# X15_Power_Plate.net
KiCad netlist of a schematic drawn in EAGLE
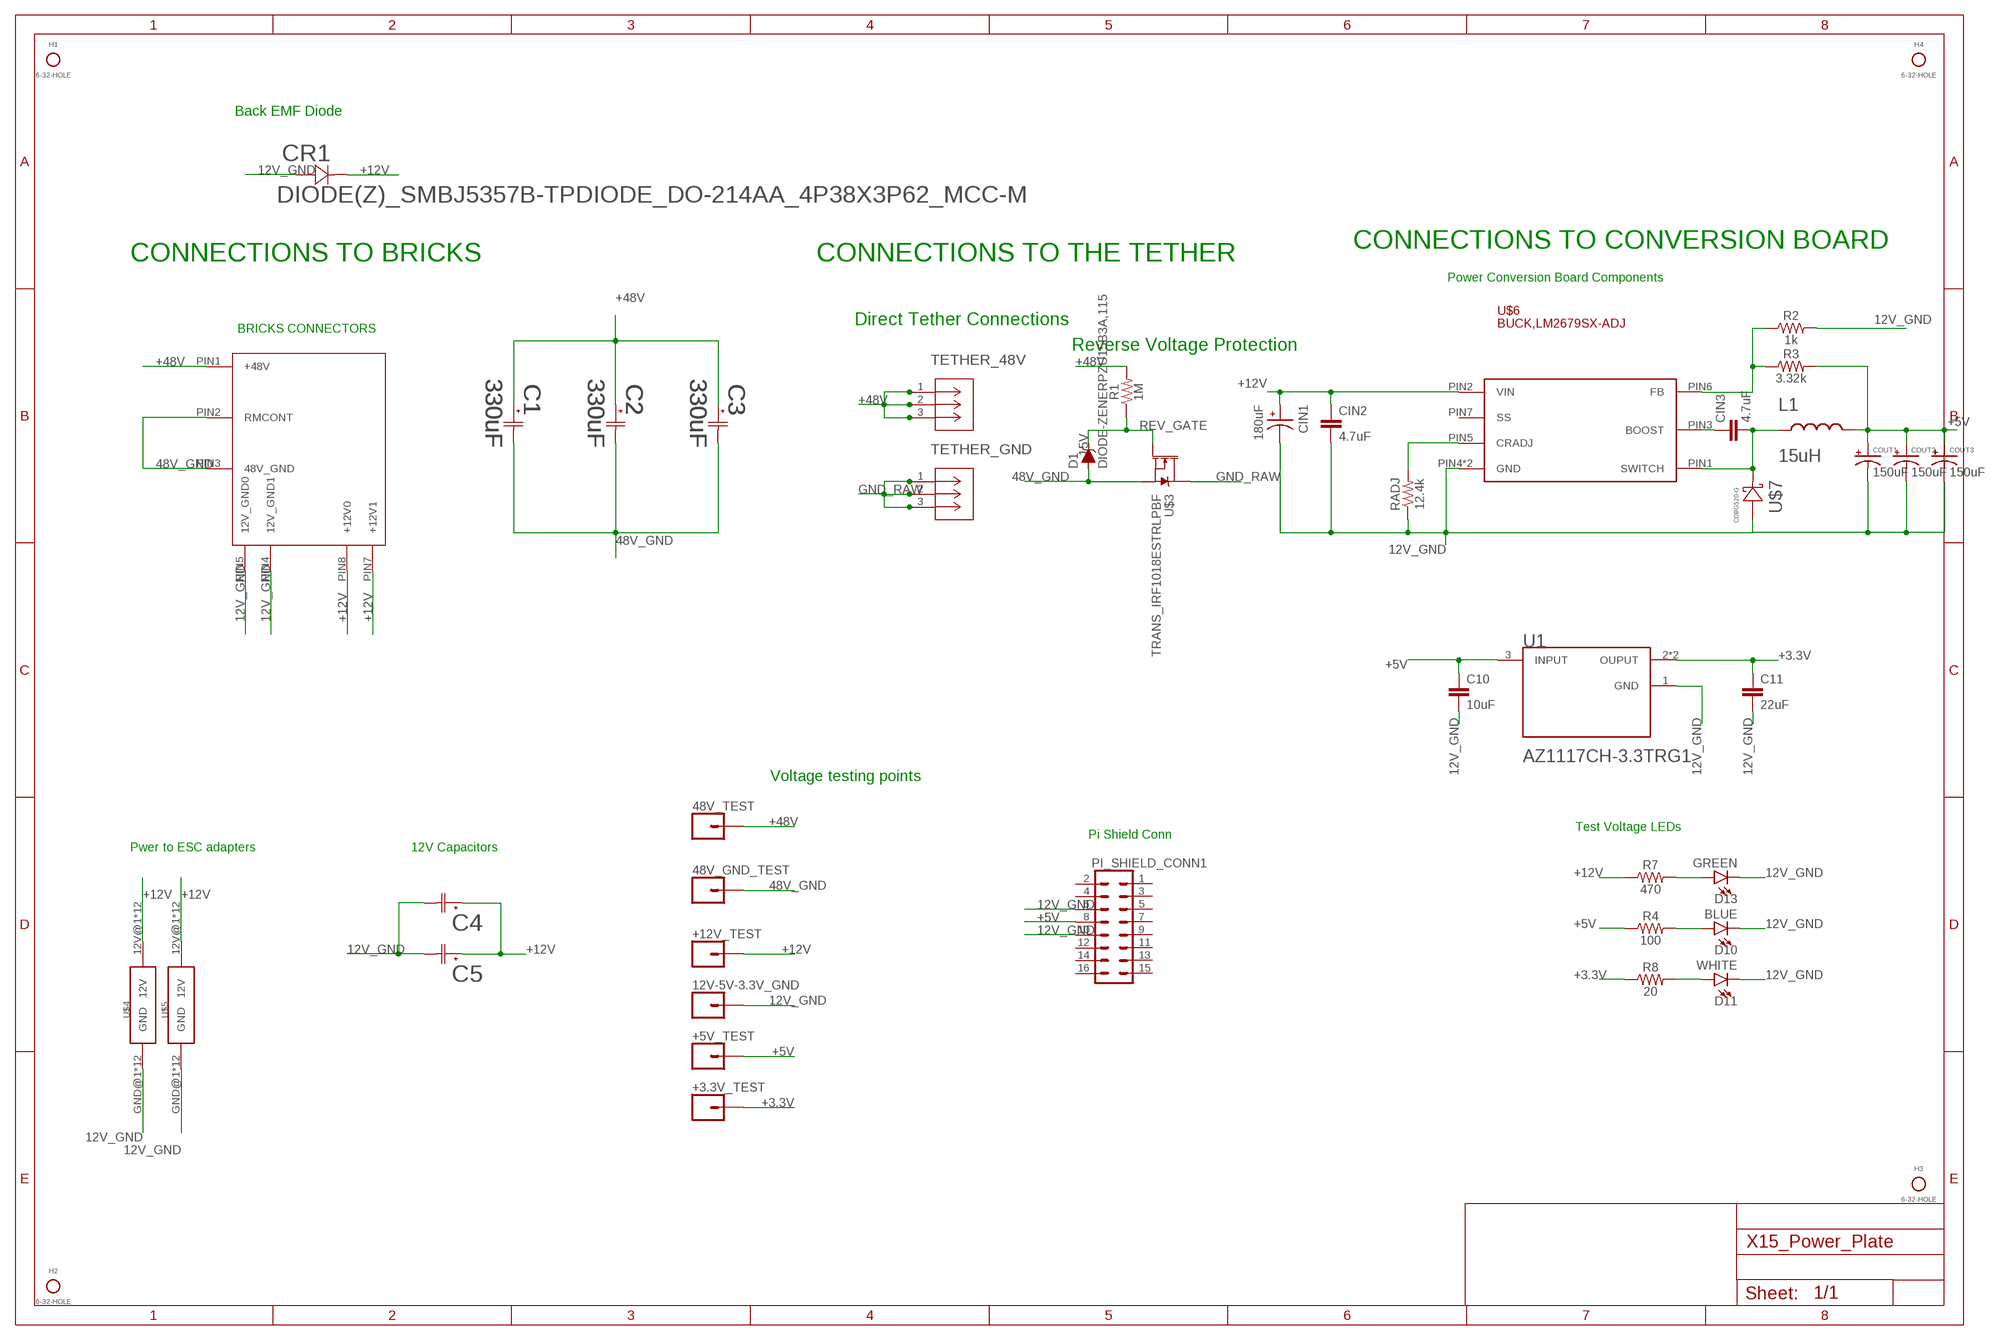
[diagram p0: schematic, sheet 1]

(export (version "E")
  (design (tool "Eeschema 10.0.6"))
  (components
    (comp (ref "+3.3V_TEST")
      (value "CONN_01")
      (footprint "eagle-import:1X01")
      (libsource (lib "eagle-import") (part "CONN_01"))
    )
    (comp (ref "+5V_TEST")
      (value "CONN_01")
      (footprint "eagle-import:1X01")
      (libsource (lib "eagle-import") (part "CONN_01"))
    )
    (comp (ref "+12V_TEST")
      (value "CONN_01")
      (footprint "eagle-import:1X01")
      (libsource (lib "eagle-import") (part "CONN_01"))
    )
    (comp (ref "12V-5V-3.3V_GND")
      (value "CONN_01")
      (footprint "eagle-import:1X01")
      (libsource (lib "eagle-import") (part "CONN_01"))
    )
    (comp (ref "48V_GND_TEST")
      (value "CONN_01")
      (footprint "eagle-import:1X01")
      (libsource (lib "eagle-import") (part "CONN_01"))
    )
    (comp (ref "48V_TEST")
      (value "CONN_01")
      (footprint "eagle-import:1X01")
      (libsource (lib "eagle-import") (part "CONN_01"))
    )
    (comp (ref "C1")
      (value "330uF")
      (footprint "eagle-import:CAP_099112E3_VIS-M")
      (fields
        (field (name "MANUFACTURER_PART_NUMBER") "MAL215099112E3")
        (field (name "COPYRIGHT") "Copyright (C) 2022 Ultra Librarian. All rights reserved.")
      )
      (libsource (lib "eagle-import") (part "CAP_MAL215099112E3CAP_099112E3_VIS-M"))
    )
    (comp (ref "C2")
      (value "330uF")
      (footprint "eagle-import:CAP_099112E3_VIS-M")
      (fields
        (field (name "MANUFACTURER_PART_NUMBER") "MAL215099112E3")
        (field (name "COPYRIGHT") "Copyright (C) 2022 Ultra Librarian. All rights reserved.")
      )
      (libsource (lib "eagle-import") (part "CAP_MAL215099112E3CAP_099112E3_VIS-M"))
    )
    (comp (ref "C3")
      (value "330uF")
      (footprint "eagle-import:CAP_099112E3_VIS-M")
      (fields
        (field (name "MANUFACTURER_PART_NUMBER") "MAL215099112E3")
        (field (name "COPYRIGHT") "Copyright (C) 2022 Ultra Librarian. All rights reserved.")
      )
      (libsource (lib "eagle-import") (part "CAP_MAL215099112E3CAP_099112E3_VIS-M"))
    )
    (comp (ref "C4")
      (value "UCV1E561MNL1GSCAP_UCD_8X10_NCH")
      (footprint "eagle-import:CAP_UCD_8X10_NCH")
      (fields
        (field (name "MANUFACTURER_PART_NUMBER") "UCV1E561MNL1GS")
        (field (name "COPYRIGHT") "Copyright (C) 2023 Ultra Librarian. All rights reserved.")
      )
      (libsource (lib "eagle-import") (part "UCV1E561MNL1GSCAP_UCD_8X10_NCH"))
    )
    (comp (ref "C5")
      (value "UCV1E561MNL1GSCAP_UCD_8X10_NCH")
      (footprint "eagle-import:CAP_UCD_8X10_NCH")
      (fields
        (field (name "MANUFACTURER_PART_NUMBER") "UCV1E561MNL1GS")
        (field (name "COPYRIGHT") "Copyright (C) 2023 Ultra Librarian. All rights reserved.")
      )
      (libsource (lib "eagle-import") (part "UCV1E561MNL1GSCAP_UCD_8X10_NCH"))
    )
    (comp (ref "C10")
      (value "10uF")
      (footprint "eagle-import:0603")
      (libsource (lib "eagle-import") (part "4.7PF-0603-50V-5%"))
    )
    (comp (ref "C11")
      (value "22uF")
      (footprint "eagle-import:0603")
      (libsource (lib "eagle-import") (part "4.7PF-0603-50V-5%"))
    )
    (comp (ref "CIN1")
      (value "180uF")
      (footprint "eagle-import:CAP_EEEFKE181XSP")
      (fields
        (field (name "DIGI-KEY_PART_NUMBER") "P18956TR-ND")
        (field (name "MF") "Panasonic")
        (field (name "MP") "EEEFKE181XSP")
      )
      (libsource (lib "eagle-import") (part "EEEFKE181XSP"))
    )
    (comp (ref "CIN2")
      (value "4.7uF")
      (footprint "eagle-import:0603")
      (libsource (lib "eagle-import") (part "4.7UF0603"))
    )
    (comp (ref "CIN3")
      (value "4.7uF")
      (footprint "eagle-import:0603")
      (libsource (lib "eagle-import") (part "4.7UF0603"))
    )
    (comp (ref "COUT1")
      (value "150uF")
      (footprint "eagle-import:2917(7343-31-METRIC)")
      (libsource (lib "eagle-import") (part "C-TANTALUM(10UF_150UF)"))
    )
    (comp (ref "COUT2")
      (value "150uF")
      (footprint "eagle-import:2917(7343-31-METRIC)")
      (libsource (lib "eagle-import") (part "C-TANTALUM(10UF_150UF)"))
    )
    (comp (ref "COUT3")
      (value "150uF")
      (footprint "eagle-import:2917(7343-31-METRIC)")
      (libsource (lib "eagle-import") (part "C-TANTALUM(10UF_150UF)"))
    )
    (comp (ref "CR1")
      (value "DIODE(Z)_SMBJ5357B-TPDIODE_DO-214AA_4P38X3P62_MCC-M")
      (footprint "eagle-import:DIODE_DO-214AA_4P38X3P62_MCC-M")
      (fields
        (field (name "MANUFACTURER_PART_NUMBER") "SMBJ5357B-TP")
        (field (name "COPYRIGHT") "Copyright (C) 2022 Ultra Librarian. All rights reserved.")
      )
      (libsource (lib "eagle-import") (part "DIODE(Z)_SMBJ5357B-TPDIODE_DO-214AA_4P38X3P62_MCC-M"))
    )
    (comp (ref "D1")
      (value "DIODE-ZENERPZU15B3A,115")
      (footprint "eagle-import:SOD-323")
      (fields (field (name "ZENER_VOLTAGE") "15V"))
      (libsource (lib "eagle-import") (part "DIODE-ZENERPZU15B3A,115"))
    )
    (comp (ref "D10")
      (value "BLUE")
      (footprint "eagle-import:LED-0603")
      (libsource (lib "eagle-import") (part "LED-BLUE0603"))
    )
    (comp (ref "D11")
      (value "WHITE")
      (footprint "eagle-import:LED-0603")
      (libsource (lib "eagle-import") (part "LED-WHITE0603"))
    )
    (comp (ref "D13")
      (value "GREEN")
      (footprint "eagle-import:LED-0603")
      (libsource (lib "eagle-import") (part "LED-GREEN0603"))
    )
    (comp (ref "H1")
      (value "6-32-HOLE")
      (footprint "eagle-import:6-32-HOLE")
      (libsource (lib "eagle-import") (part "6-32-HOLE"))
    )
    (comp (ref "H2")
      (value "6-32-HOLE")
      (footprint "eagle-import:6-32-HOLE")
      (libsource (lib "eagle-import") (part "6-32-HOLE"))
    )
    (comp (ref "H3")
      (value "6-32-HOLE")
      (footprint "eagle-import:6-32-HOLE")
      (libsource (lib "eagle-import") (part "6-32-HOLE"))
    )
    (comp (ref "H4")
      (value "6-32-HOLE")
      (footprint "eagle-import:6-32-HOLE")
      (libsource (lib "eagle-import") (part "6-32-HOLE"))
    )
    (comp (ref "L1")
      (value "15uH")
      (footprint "eagle-import:HCMA1305")
      (libsource (lib "eagle-import") (part "HCMA1305"))
    )
    (comp (ref "PI_SHIELD_CONN1")
      (value "8X_CONN")
      (footprint "eagle-import:IPL7X2")
      (libsource (lib "eagle-import") (part "8X_CONN"))
    )
    (comp (ref "R1")
      (value "1M")
      (footprint "eagle-import:0603")
      (libsource (lib "eagle-import") (part "1MOHM-0603-1/4W-5%"))
    )
    (comp (ref "R2")
      (value "1k")
      (footprint "eagle-import:0603")
      (libsource (lib "eagle-import") (part "2.0KOHM-0603-1/10W-5%"))
    )
    (comp (ref "R3")
      (value "3.32k")
      (footprint "eagle-import:0603")
      (libsource (lib "eagle-import") (part "2.0KOHM-0603-1/10W-5%"))
    )
    (comp (ref "R4")
      (value "100")
      (footprint "eagle-import:0603")
      (libsource (lib "eagle-import") (part "100OHM-0603-1/4W-5%"))
    )
    (comp (ref "R7")
      (value "470")
      (footprint "eagle-import:0603")
      (libsource (lib "eagle-import") (part "470OHM-0603-1/10W-1%"))
    )
    (comp (ref "R8")
      (value "20")
      (footprint "eagle-import:0603")
      (libsource (lib "eagle-import") (part "20OHM-0603-1/10W-1%"))
    )
    (comp (ref "RADJ")
      (value "12.4k")
      (footprint "eagle-import:0603")
      (libsource (lib "eagle-import") (part "2.0KOHM-0603-1/10W-5%"))
    )
    (comp (ref "TETHER_48V")
      (value "796636-3(TETHER)")
      (footprint "eagle-import:CON3_P5MM_VER_TERM-BLK_TYC")
      (fields
        (field (name "MANUFACTURER_PART_NUMBER") "796636-3")
        (field (name "COPYRIGHT") "Copyright (C) 2022 Ultra Librarian. All rights reserved.")
      )
      (libsource (lib "eagle-import") (part "796636-3(TETHER)"))
    )
    (comp (ref "TETHER_GND")
      (value "796636-3(TETHER)")
      (footprint "eagle-import:CON3_P5MM_VER_TERM-BLK_TYC")
      (fields
        (field (name "MANUFACTURER_PART_NUMBER") "796636-3")
        (field (name "COPYRIGHT") "Copyright (C) 2022 Ultra Librarian. All rights reserved.")
      )
      (libsource (lib "eagle-import") (part "796636-3(TETHER)"))
    )
    (comp (ref "U$2")
      (value "CONN_BMR480_CONNECTOR")
      (footprint "eagle-import:BMR480_CONNECTOR")
      (libsource (lib "eagle-import") (part "CONN_BMR480_CONNECTOR"))
    )
    (comp (ref "U$3")
      (value "TRANS_IRF1018ESTRLPBF")
      (footprint "eagle-import:D2PAK")
      (libsource (lib "eagle-import") (part "TRANS_IRF1018EPBF"))
    )
    (comp (ref "U$4")
      (value "BACKPLANE_ESC_ADAPTER_PWRBKP")
      (footprint "eagle-import:BACKPLANE_ESC_ADAPTER_BKP_PWR")
      (libsource (lib "eagle-import") (part "BACKPLANE_ESC_ADAPTER_PWRBKP"))
    )
    (comp (ref "U$5")
      (value "BACKPLANE_ESC_ADAPTER_PWRBKP")
      (footprint "eagle-import:BACKPLANE_ESC_ADAPTER_BKP_PWR")
      (libsource (lib "eagle-import") (part "BACKPLANE_ESC_ADAPTER_PWRBKP"))
    )
    (comp (ref "U$6")
      (value "BUCK,LM2679SX-ADJ")
      (footprint "eagle-import:BUCK,LM2679SX-ADJ")
      (libsource (lib "eagle-import") (part "BUCK,LM2679SX-ADJ"))
    )
    (comp (ref "U$7")
      (value "CDBG520-G")
      (footprint "eagle-import:DO214AC")
      (libsource (lib "eagle-import") (part "CDBG520-G"))
    )
    (comp (ref "U1")
      (value "LINEAR,AZ1117CR-3.3TRG1DIODES_AZ1117CH-3.3TRG1_0_0")
      (footprint "eagle-import:LINEAR,AZ1117CR-3.3TRG1")
      (fields (field (name "MF") "Diodes Inc.") (field (name "MP") "AZ1117CH-3.3TRG1"))
      (libsource (lib "eagle-import") (part "LINEAR,AZ1117CR-3.3TRG1DIODES_AZ1117CH-3.3TRG1_0_0"))
    )
  )
  (nets
    (net (code "1") (name "/+3.3V") (class "Default")
      (node (ref "+3.3V_TEST") (pin "1") (pinfunction "1_1") (pintype "passive"))
      (node (ref "C11") (pin "1") (pinfunction "1_1") (pintype "passive"))
      (node (ref "R8") (pin "1") (pinfunction "1_1") (pintype "passive"))
      (node (ref "U1") (pin "2") (pinfunction "OUPUT_2") (pintype "output"))
      (node (ref "U1") (pin "4") (pinfunction "OUPUT_4") (pintype "output"))
    )
    (net (code "2") (name "/+5V") (class "Default")
      (node (ref "+5V_TEST") (pin "1") (pinfunction "1_1") (pintype "passive"))
      (node (ref "C10") (pin "1") (pinfunction "1_1") (pintype "passive"))
      (node (ref "COUT1") (pin "+") (pinfunction "+_+") (pintype "passive"))
      (node (ref "COUT2") (pin "+") (pinfunction "+_+") (pintype "passive"))
      (node (ref "COUT3") (pin "+") (pinfunction "+_+") (pintype "passive"))
      (node (ref "L1") (pin "2") (pinfunction "2_2") (pintype "passive"))
      (node (ref "PI_SHIELD_CONN1") (pin "8") (pinfunction "19_8") (pintype "passive"))
      (node (ref "R3") (pin "2") (pinfunction "2_2") (pintype "passive"))
      (node (ref "R4") (pin "1") (pinfunction "1_1") (pintype "passive"))
      (node (ref "U1") (pin "3") (pinfunction "INPUT_3") (pintype "input"))
    )
    (net (code "3") (name "/+12V") (class "Default")
      (node (ref "+12V_TEST") (pin "1") (pinfunction "1_1") (pintype "passive"))
      (node (ref "C4") (pin "1") (pinfunction "1_1") (pintype "passive"))
      (node (ref "C5") (pin "1") (pinfunction "1_1") (pintype "passive"))
      (node (ref "CIN1") (pin "1") (pinfunction "1_1") (pintype "passive"))
      (node (ref "CIN2") (pin "1") (pinfunction "1_1") (pintype "passive"))
      (node (ref "CR1") (pin "1") (pinfunction "1_1") (pintype "passive"))
      (node (ref "R7") (pin "1") (pinfunction "1_1") (pintype "passive"))
      (node (ref "U$2") (pin "PIN7") (pinfunction "+12V1_PIN7") (pintype "bidirectional"))
      (node (ref "U$2") (pin "PIN8") (pinfunction "+12V0_PIN8") (pintype "bidirectional"))
      (node (ref "U$4") (pin "12V@1") (pinfunction "12V_12V@1") (pintype "bidirectional"))
      (node (ref "U$4") (pin "12V@10") (pinfunction "12V_12V@10") (pintype "bidirectional"))
      (node (ref "U$4") (pin "12V@11") (pinfunction "12V_12V@11") (pintype "bidirectional"))
      (node (ref "U$4") (pin "12V@12") (pinfunction "12V_12V@12") (pintype "bidirectional"))
      (node (ref "U$4") (pin "12V@2") (pinfunction "12V_12V@2") (pintype "bidirectional"))
      (node (ref "U$4") (pin "12V@3") (pinfunction "12V_12V@3") (pintype "bidirectional"))
      (node (ref "U$4") (pin "12V@4") (pinfunction "12V_12V@4") (pintype "bidirectional"))
      (node (ref "U$4") (pin "12V@5") (pinfunction "12V_12V@5") (pintype "bidirectional"))
      (node (ref "U$4") (pin "12V@6") (pinfunction "12V_12V@6") (pintype "bidirectional"))
      (node (ref "U$4") (pin "12V@7") (pinfunction "12V_12V@7") (pintype "bidirectional"))
      (node (ref "U$4") (pin "12V@8") (pinfunction "12V_12V@8") (pintype "bidirectional"))
      (node (ref "U$4") (pin "12V@9") (pinfunction "12V_12V@9") (pintype "bidirectional"))
      (node (ref "U$5") (pin "12V@1") (pinfunction "12V_12V@1") (pintype "bidirectional"))
      (node (ref "U$5") (pin "12V@10") (pinfunction "12V_12V@10") (pintype "bidirectional"))
      (node (ref "U$5") (pin "12V@11") (pinfunction "12V_12V@11") (pintype "bidirectional"))
      (node (ref "U$5") (pin "12V@12") (pinfunction "12V_12V@12") (pintype "bidirectional"))
      (node (ref "U$5") (pin "12V@2") (pinfunction "12V_12V@2") (pintype "bidirectional"))
      (node (ref "U$5") (pin "12V@3") (pinfunction "12V_12V@3") (pintype "bidirectional"))
      (node (ref "U$5") (pin "12V@4") (pinfunction "12V_12V@4") (pintype "bidirectional"))
      (node (ref "U$5") (pin "12V@5") (pinfunction "12V_12V@5") (pintype "bidirectional"))
      (node (ref "U$5") (pin "12V@6") (pinfunction "12V_12V@6") (pintype "bidirectional"))
      (node (ref "U$5") (pin "12V@7") (pinfunction "12V_12V@7") (pintype "bidirectional"))
      (node (ref "U$5") (pin "12V@8") (pinfunction "12V_12V@8") (pintype "bidirectional"))
      (node (ref "U$5") (pin "12V@9") (pinfunction "12V_12V@9") (pintype "bidirectional"))
      (node (ref "U$6") (pin "PIN2") (pinfunction "VIN_PIN2") (pintype "bidirectional"))
    )
    (net (code "4") (name "/+48V") (class "Default")
      (node (ref "48V_TEST") (pin "1") (pinfunction "1_1") (pintype "passive"))
      (node (ref "C1") (pin "1") (pinfunction "1_1") (pintype "passive"))
      (node (ref "C2") (pin "1") (pinfunction "1_1") (pintype "passive"))
      (node (ref "C3") (pin "1") (pinfunction "1_1") (pintype "passive"))
      (node (ref "R1") (pin "2") (pinfunction "2_2") (pintype "passive"))
      (node (ref "TETHER_48V") (pin "1") (pinfunction "1_1") (pintype "passive"))
      (node (ref "TETHER_48V") (pin "2") (pinfunction "2_2") (pintype "passive"))
      (node (ref "TETHER_48V") (pin "3") (pinfunction "3_3") (pintype "passive"))
      (node (ref "U$2") (pin "PIN1") (pinfunction "+48V_PIN1") (pintype "bidirectional"))
    )
    (net (code "5") (name "/12V_GND") (class "Default")
      (node (ref "12V-5V-3.3V_GND") (pin "1") (pinfunction "1_1") (pintype "passive"))
      (node (ref "C10") (pin "2") (pinfunction "2_2") (pintype "passive"))
      (node (ref "C11") (pin "2") (pinfunction "2_2") (pintype "passive"))
      (node (ref "C4") (pin "2") (pinfunction "2_2") (pintype "passive"))
      (node (ref "C5") (pin "2") (pinfunction "2_2") (pintype "passive"))
      (node (ref "CIN1") (pin "2") (pinfunction "2_2") (pintype "passive"))
      (node (ref "CIN2") (pin "2") (pinfunction "2_2") (pintype "passive"))
      (node (ref "COUT1") (pin "-") (pinfunction "-_-") (pintype "passive"))
      (node (ref "COUT2") (pin "-") (pinfunction "-_-") (pintype "passive"))
      (node (ref "COUT3") (pin "-") (pinfunction "-_-") (pintype "passive"))
      (node (ref "CR1") (pin "2") (pinfunction "2_2") (pintype "passive"))
      (node (ref "D10") (pin "C") (pinfunction "C_C") (pintype "passive"))
      (node (ref "D11") (pin "C") (pinfunction "C_C") (pintype "passive"))
      (node (ref "D13") (pin "C") (pinfunction "C_C") (pintype "passive"))
      (node (ref "PI_SHIELD_CONN1") (pin "10") (pinfunction "21_10") (pintype "passive"))
      (node (ref "PI_SHIELD_CONN1") (pin "6") (pinfunction "17_6") (pintype "passive"))
      (node (ref "R2") (pin "2") (pinfunction "2_2") (pintype "passive"))
      (node (ref "RADJ") (pin "1") (pinfunction "1_1") (pintype "passive"))
      (node (ref "U$2") (pin "PIN4") (pinfunction "12V_GND1_PIN4") (pintype "bidirectional"))
      (node (ref "U$2") (pin "PIN5") (pinfunction "12V_GND0_PIN5") (pintype "bidirectional"))
      (node (ref "U$4") (pin "GND@1") (pinfunction "GND_GND@1") (pintype "bidirectional"))
      (node (ref "U$4") (pin "GND@10") (pinfunction "GND_GND@10") (pintype "bidirectional"))
      (node (ref "U$4") (pin "GND@11") (pinfunction "GND_GND@11") (pintype "bidirectional"))
      (node (ref "U$4") (pin "GND@12") (pinfunction "GND_GND@12") (pintype "bidirectional"))
      (node (ref "U$4") (pin "GND@2") (pinfunction "GND_GND@2") (pintype "bidirectional"))
      (node (ref "U$4") (pin "GND@3") (pinfunction "GND_GND@3") (pintype "bidirectional"))
      (node (ref "U$4") (pin "GND@4") (pinfunction "GND_GND@4") (pintype "bidirectional"))
      (node (ref "U$4") (pin "GND@5") (pinfunction "GND_GND@5") (pintype "bidirectional"))
      (node (ref "U$4") (pin "GND@6") (pinfunction "GND_GND@6") (pintype "bidirectional"))
      (node (ref "U$4") (pin "GND@7") (pinfunction "GND_GND@7") (pintype "bidirectional"))
      (node (ref "U$4") (pin "GND@8") (pinfunction "GND_GND@8") (pintype "bidirectional"))
      (node (ref "U$4") (pin "GND@9") (pinfunction "GND_GND@9") (pintype "bidirectional"))
      (node (ref "U$5") (pin "GND@1") (pinfunction "GND_GND@1") (pintype "bidirectional"))
      (node (ref "U$5") (pin "GND@10") (pinfunction "GND_GND@10") (pintype "bidirectional"))
      (node (ref "U$5") (pin "GND@11") (pinfunction "GND_GND@11") (pintype "bidirectional"))
      (node (ref "U$5") (pin "GND@12") (pinfunction "GND_GND@12") (pintype "bidirectional"))
      (node (ref "U$5") (pin "GND@2") (pinfunction "GND_GND@2") (pintype "bidirectional"))
      (node (ref "U$5") (pin "GND@3") (pinfunction "GND_GND@3") (pintype "bidirectional"))
      (node (ref "U$5") (pin "GND@4") (pinfunction "GND_GND@4") (pintype "bidirectional"))
      (node (ref "U$5") (pin "GND@5") (pinfunction "GND_GND@5") (pintype "bidirectional"))
      (node (ref "U$5") (pin "GND@6") (pinfunction "GND_GND@6") (pintype "bidirectional"))
      (node (ref "U$5") (pin "GND@7") (pinfunction "GND_GND@7") (pintype "bidirectional"))
      (node (ref "U$5") (pin "GND@8") (pinfunction "GND_GND@8") (pintype "bidirectional"))
      (node (ref "U$5") (pin "GND@9") (pinfunction "GND_GND@9") (pintype "bidirectional"))
      (node (ref "U$6") (pin "PIN4") (pinfunction "GND_PIN4") (pintype "bidirectional"))
      (node (ref "U$6") (pin "PIN8") (pinfunction "GND_PIN8") (pintype "bidirectional"))
      (node (ref "U$7") (pin "A") (pinfunction "2_A") (pintype "passive"))
      (node (ref "U1") (pin "1") (pinfunction "GND_1") (pintype "input"))
    )
    (net (code "6") (name "/48V_GND") (class "Default")
      (node (ref "48V_GND_TEST") (pin "1") (pinfunction "1_1") (pintype "passive"))
      (node (ref "C1") (pin "2") (pinfunction "2_2") (pintype "passive"))
      (node (ref "C2") (pin "2") (pinfunction "2_2") (pintype "passive"))
      (node (ref "C3") (pin "2") (pinfunction "2_2") (pintype "passive"))
      (node (ref "D1") (pin "A") (pinfunction "A_A") (pintype "passive"))
      (node (ref "U$2") (pin "PIN2") (pinfunction "RMCONT_PIN2") (pintype "bidirectional"))
      (node (ref "U$2") (pin "PIN3") (pinfunction "48V_GND_PIN3") (pintype "bidirectional"))
      (node (ref "U$3") (pin "2") (pinfunction "S_2") (pintype "bidirectional"))
    )
    (net (code "7") (name "/GND_RAW") (class "Default")
      (node (ref "TETHER_GND") (pin "1") (pinfunction "1_1") (pintype "passive"))
      (node (ref "TETHER_GND") (pin "2") (pinfunction "2_2") (pintype "passive"))
      (node (ref "TETHER_GND") (pin "3") (pinfunction "3_3") (pintype "passive"))
      (node (ref "U$3") (pin "3") (pinfunction "D_3") (pintype "bidirectional"))
    )
    (net (code "8") (name "/REV_GATE") (class "Default")
      (node (ref "D1") (pin "C") (pinfunction "C_C") (pintype "passive"))
      (node (ref "R1") (pin "1") (pinfunction "1_1") (pintype "passive"))
      (node (ref "U$3") (pin "1") (pinfunction "G_1") (pintype "bidirectional"))
    )
    (net (code "9") (name "Net-(D10-PadA)") (class "Default")
      (node (ref "D10") (pin "A") (pinfunction "A_A") (pintype "passive"))
      (node (ref "R4") (pin "2") (pinfunction "2_2") (pintype "passive"))
    )
    (net (code "10") (name "Net-(D11-PadA)") (class "Default")
      (node (ref "D11") (pin "A") (pinfunction "A_A") (pintype "passive"))
      (node (ref "R8") (pin "2") (pinfunction "2_2") (pintype "passive"))
    )
    (net (code "11") (name "Net-(D13-PadA)") (class "Default")
      (node (ref "D13") (pin "A") (pinfunction "A_A") (pintype "passive"))
      (node (ref "R7") (pin "2") (pinfunction "2_2") (pintype "passive"))
    )
    (net (code "12") (name "Net-(U$6-BOOST)") (class "Default")
      (node (ref "CIN3") (pin "1") (pinfunction "1_1") (pintype "passive"))
      (node (ref "U$6") (pin "PIN3") (pinfunction "BOOST_PIN3") (pintype "bidirectional"))
    )
    (net (code "13") (name "Net-(U$6-CRADJ)") (class "Default")
      (node (ref "RADJ") (pin "2") (pinfunction "2_2") (pintype "passive"))
      (node (ref "U$6") (pin "PIN5") (pinfunction "CRADJ_PIN5") (pintype "bidirectional"))
    )
    (net (code "14") (name "Net-(U$6-FB)") (class "Default")
      (node (ref "R2") (pin "1") (pinfunction "1_1") (pintype "passive"))
      (node (ref "R3") (pin "1") (pinfunction "1_1") (pintype "passive"))
      (node (ref "U$6") (pin "PIN6") (pinfunction "FB_PIN6") (pintype "bidirectional"))
    )
    (net (code "15") (name "Net-(U$6-SWITCH)") (class "Default")
      (node (ref "CIN3") (pin "2") (pinfunction "2_2") (pintype "passive"))
      (node (ref "L1") (pin "1") (pinfunction "1_1") (pintype "passive"))
      (node (ref "U$6") (pin "PIN1") (pinfunction "SWITCH_PIN1") (pintype "bidirectional"))
      (node (ref "U$7") (pin "C") (pinfunction "1_C") (pintype "passive"))
    )
    (net (code "16") (name "unconnected-(PI_SHIELD_CONN1-1-Pad13)") (class "Default")
      (node (ref "PI_SHIELD_CONN1") (pin "13") (pinfunction "1_13") (pintype "passive"))
    )
    (net (code "17") (name "unconnected-(PI_SHIELD_CONN1-2-Pad14)") (class "Default")
      (node (ref "PI_SHIELD_CONN1") (pin "14") (pinfunction "2_14") (pintype "passive"))
    )
    (net (code "18") (name "unconnected-(PI_SHIELD_CONN1-3-Pad16)") (class "Default")
      (node (ref "PI_SHIELD_CONN1") (pin "16") (pinfunction "3_16") (pintype "passive"))
    )
    (net (code "19") (name "unconnected-(PI_SHIELD_CONN1-4-Pad15)") (class "Default")
      (node (ref "PI_SHIELD_CONN1") (pin "15") (pinfunction "4_15") (pintype "passive"))
    )
    (net (code "20") (name "unconnected-(PI_SHIELD_CONN1-13-Pad2)") (class "Default")
      (node (ref "PI_SHIELD_CONN1") (pin "2") (pinfunction "13_2") (pintype "passive"))
    )
    (net (code "21") (name "unconnected-(PI_SHIELD_CONN1-14-Pad1)") (class "Default")
      (node (ref "PI_SHIELD_CONN1") (pin "1") (pinfunction "14_1") (pintype "passive"))
    )
    (net (code "22") (name "unconnected-(PI_SHIELD_CONN1-15-Pad4)") (class "Default")
      (node (ref "PI_SHIELD_CONN1") (pin "4") (pinfunction "15_4") (pintype "passive"))
    )
    (net (code "23") (name "unconnected-(PI_SHIELD_CONN1-16-Pad3)") (class "Default")
      (node (ref "PI_SHIELD_CONN1") (pin "3") (pinfunction "16_3") (pintype "passive"))
    )
    (net (code "24") (name "unconnected-(PI_SHIELD_CONN1-18-Pad5)") (class "Default")
      (node (ref "PI_SHIELD_CONN1") (pin "5") (pinfunction "18_5") (pintype "passive"))
    )
    (net (code "25") (name "unconnected-(PI_SHIELD_CONN1-20-Pad7)") (class "Default")
      (node (ref "PI_SHIELD_CONN1") (pin "7") (pinfunction "20_7") (pintype "passive"))
    )
    (net (code "26") (name "unconnected-(PI_SHIELD_CONN1-22-Pad9)") (class "Default")
      (node (ref "PI_SHIELD_CONN1") (pin "9") (pinfunction "22_9") (pintype "passive"))
    )
    (net (code "27") (name "unconnected-(PI_SHIELD_CONN1-23-Pad12)") (class "Default")
      (node (ref "PI_SHIELD_CONN1") (pin "12") (pinfunction "23_12") (pintype "passive"))
    )
    (net (code "28") (name "unconnected-(PI_SHIELD_CONN1-24-Pad11)") (class "Default")
      (node (ref "PI_SHIELD_CONN1") (pin "11") (pinfunction "24_11") (pintype "passive"))
    )
    (net (code "29") (name "unconnected-(U$6-SS-PadPIN7)") (class "Default")
      (node (ref "U$6") (pin "PIN7") (pinfunction "SS_PIN7") (pintype "bidirectional"))
    )
  )
)
